# easyeda-standard-schematic.net
KiCad netlist of a schematic drawn in EasyEDA
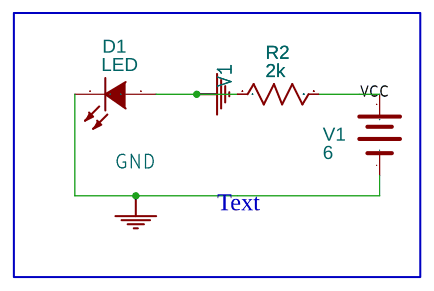
[diagram p0: schematic sheet]

(export (version "E")
  (design (tool "Eeschema 10.0.6"))
  (components
    (comp (ref "D1") (value "LED") (libsource (lib "") (part "LED")))
    (comp (ref "R2") (value "2k") (libsource (lib "") (part "Resistor")))
    (comp (ref "V1") (value "6") (libsource (lib "") (part "Battery")))
  )
  (nets
    (net (code "1") (name "/VCC") (class "Default")
      (node (ref "R2") (pin "2") (pinfunction "2_2") (pintype "unspecified"))
      (node (ref "V1") (pin "+") (pinfunction "+_+") (pintype "unspecified"))
    )
    (net (code "2") (name "GND") (class "Default")
      (node (ref "D1") (pin "K") (pinfunction "K_K") (pintype "unspecified"))
      (node (ref "V1") (pin "-") (pinfunction "-_-") (pintype "unspecified"))
    )
    (net (code "3") (name "V1") (class "Default")
      (node (ref "D1") (pin "A") (pinfunction "A_A") (pintype "unspecified"))
      (node (ref "R2") (pin "1") (pinfunction "1_1") (pintype "unspecified"))
    )
  )
)
